# TrebleBoost.net
KiCad netlist of a schematic drawn in Altium Designer
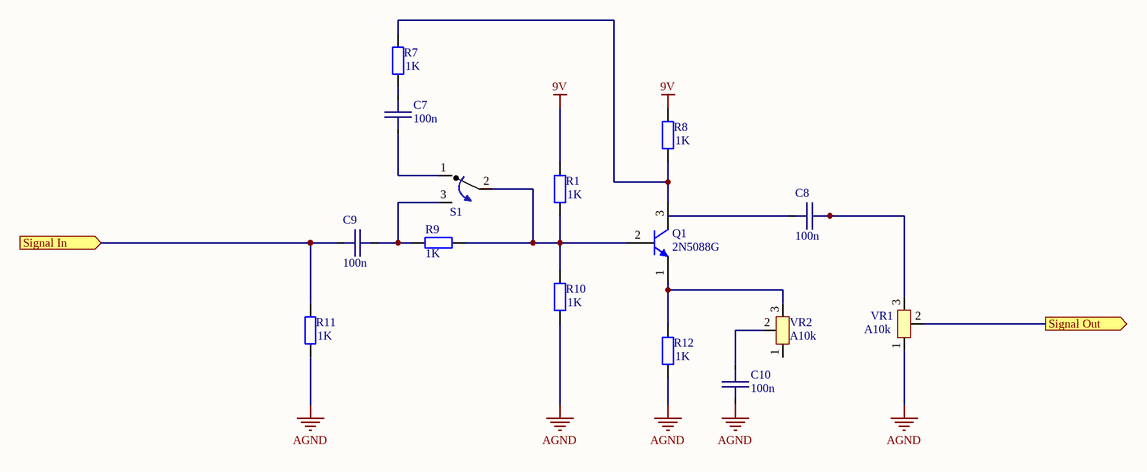
[diagram p0: TrebleBoost.SchDoc]

(export (version "E")
  (design (tool "Eeschema 10.0.6"))
  (components
    (comp (ref "C7")
      (value "100n")
      (footprint "Cap-0.2\"")
      (fields (field (name "Comment") "Wima Capacitor"))
      (libsource (lib "Parts") (part "Wima Capacitor"))
    )
    (comp (ref "C8")
      (value "100n")
      (footprint "Cap-0.2\"")
      (fields (field (name "Comment") "Wima Capacitor"))
      (libsource (lib "Parts") (part "Wima Capacitor"))
    )
    (comp (ref "C9")
      (value "100n")
      (footprint "Cap-0.2\"")
      (fields (field (name "Comment") "Wima Capacitor"))
      (libsource (lib "Parts") (part "Wima Capacitor"))
    )
    (comp (ref "C10")
      (value "100n")
      (footprint "Cap-0.2\"")
      (fields (field (name "Comment") "Wima Capacitor"))
      (libsource (lib "Parts") (part "Wima Capacitor"))
    )
    (comp (ref "Q1")
      (value "2N5088G")
      (footprint "ONSC-TO-92-3-29-11")
      (description "Amplifier Transistor, NPN Silicon, 3-Pin TO-92, Pb-Free, Bulk Box")
      (fields (field (name "MANUFACTURER") "On Semiconductor"))
      (libsource (lib "ON Semi General Purpose Transistors") (part "2N5088G"))
    )
    (comp (ref "R1")
      (value "1K")
      (footprint "AXIAL-0.4")
      (description "Resistor")
      (fields (field (name "Comment") "Res2") (field (name "PUBLISHER") "Altium Limited"))
      (libsource (lib "Miscellaneous Devices") (part "Res2"))
    )
    (comp (ref "R7")
      (value "1K")
      (footprint "AXIAL-0.4")
      (description "Resistor")
      (fields (field (name "Comment") "Res2") (field (name "PUBLISHER") "Altium Limited"))
      (libsource (lib "Miscellaneous Devices") (part "Res2"))
    )
    (comp (ref "R8")
      (value "1K")
      (footprint "AXIAL-0.4")
      (description "Resistor")
      (fields (field (name "Comment") "Res2") (field (name "PUBLISHER") "Altium Limited"))
      (libsource (lib "Miscellaneous Devices") (part "Res2"))
    )
    (comp (ref "R9")
      (value "1K")
      (footprint "AXIAL-0.4")
      (description "Resistor")
      (fields (field (name "Comment") "Res2") (field (name "PUBLISHER") "Altium Limited"))
      (libsource (lib "") (part "Res2_1"))
    )
    (comp (ref "R10")
      (value "1K")
      (footprint "AXIAL-0.4")
      (description "Resistor")
      (fields (field (name "Comment") "Res2") (field (name "PUBLISHER") "Altium Limited"))
      (libsource (lib "Miscellaneous Devices") (part "Res2"))
    )
    (comp (ref "R11")
      (value "1K")
      (footprint "AXIAL-0.4")
      (description "Resistor")
      (fields (field (name "Comment") "Res2") (field (name "PUBLISHER") "Altium Limited"))
      (libsource (lib "Miscellaneous Devices") (part "Res2"))
    )
    (comp (ref "R12")
      (value "1K")
      (footprint "AXIAL-0.4")
      (description "Resistor")
      (fields (field (name "Comment") "Res2") (field (name "PUBLISHER") "Altium Limited"))
      (libsource (lib "Miscellaneous Devices") (part "Res2"))
    )
    (comp (ref "S1")
      (value "SPDT Toggle")
      (footprint "SPDT Toggle")
      (libsource (lib "Parts") (part "SPDT Toggle"))
    )
    (comp (ref "VR1")
      (value "A10k")
      (footprint "Pot-16mm")
      (fields (field (name "Comment") "Pot-16mm"))
      (libsource (lib "") (part "Pot-16mm_1"))
    )
    (comp (ref "VR2")
      (value "A10k")
      (footprint "Pot-16mm")
      (fields (field (name "Comment") "Pot-16mm"))
      (libsource (lib "Parts") (part "Pot-16mm"))
    )
  )
  (nets
    (net (code "1") (name "/Signal In") (class "Default")
      (node (ref "C9") (pin "2") (pinfunction "2_2") (pintype "passive"))
      (node (ref "R11") (pin "2") (pinfunction "2_2") (pintype "passive"))
    )
    (net (code "2") (name "/Signal Out") (class "Default")
      (node (ref "VR1") (pin "2") (pinfunction "2_2") (pintype "passive"))
    )
    (net (code "3") (name "9V") (class "Default")
      (node (ref "R1") (pin "2") (pinfunction "2_2") (pintype "passive"))
      (node (ref "R8") (pin "2") (pinfunction "2_2") (pintype "passive"))
    )
    (net (code "4") (name "AGND") (class "Default")
      (node (ref "C10") (pin "1") (pinfunction "1_1") (pintype "passive"))
      (node (ref "R10") (pin "1") (pinfunction "1_1") (pintype "passive"))
      (node (ref "R11") (pin "1") (pinfunction "1_1") (pintype "passive"))
      (node (ref "R12") (pin "1") (pinfunction "1_1") (pintype "passive"))
      (node (ref "VR1") (pin "1") (pinfunction "1_1") (pintype "passive"))
    )
    (net (code "5") (name "Net-(C7-Pad1)") (class "Default")
      (node (ref "C7") (pin "1") (pinfunction "1_1") (pintype "passive"))
      (node (ref "R7") (pin "1") (pinfunction "1_1") (pintype "passive"))
    )
    (net (code "6") (name "Net-(C7-Pad2)") (class "Default")
      (node (ref "C7") (pin "2") (pinfunction "2_2") (pintype "passive"))
      (node (ref "S1") (pin "1") (pinfunction "1_1") (pintype "passive"))
    )
    (net (code "7") (name "Net-(C8-Pad1)") (class "Default")
      (node (ref "C8") (pin "1") (pinfunction "1_1") (pintype "passive"))
      (node (ref "VR1") (pin "3") (pinfunction "3_3") (pintype "passive"))
    )
    (net (code "8") (name "Net-(C9-Pad1)") (class "Default")
      (node (ref "C9") (pin "1") (pinfunction "1_1") (pintype "passive"))
      (node (ref "R9") (pin "2") (pinfunction "2_2") (pintype "passive"))
      (node (ref "S1") (pin "3") (pinfunction "3_3") (pintype "passive"))
    )
    (net (code "9") (name "Net-(C10-Pad2)") (class "Default")
      (node (ref "C10") (pin "2") (pinfunction "2_2") (pintype "passive"))
      (node (ref "VR2") (pin "2") (pinfunction "2_2") (pintype "passive"))
    )
    (net (code "10") (name "Net-(Q1-B)") (class "Default")
      (node (ref "Q1") (pin "2") (pinfunction "B_2") (pintype "passive"))
      (node (ref "R1") (pin "1") (pinfunction "1_1") (pintype "passive"))
      (node (ref "R10") (pin "2") (pinfunction "2_2") (pintype "passive"))
      (node (ref "R9") (pin "1") (pinfunction "1_1") (pintype "passive"))
      (node (ref "S1") (pin "2") (pinfunction "2_2") (pintype "passive"))
    )
    (net (code "11") (name "Net-(Q1-C)") (class "Default")
      (node (ref "Q1") (pin "3") (pinfunction "C_3") (pintype "passive"))
      (node (ref "R7") (pin "2") (pinfunction "2_2") (pintype "passive"))
      (node (ref "R8") (pin "1") (pinfunction "1_1") (pintype "passive"))
    )
    (net (code "12") (name "Net-(Q1-E)") (class "Default")
      (node (ref "Q1") (pin "1") (pinfunction "E_1") (pintype "passive"))
      (node (ref "R12") (pin "2") (pinfunction "2_2") (pintype "passive"))
      (node (ref "VR2") (pin "3") (pinfunction "3_3") (pintype "passive"))
    )
    (net (code "13") (name "unconnected-(C8-Pad2)") (class "Default")
      (node (ref "C8") (pin "2") (pinfunction "2_2") (pintype "passive"))
    )
    (net (code "14") (name "unconnected-(VR2-Pad1)") (class "Default")
      (node (ref "VR2") (pin "1") (pinfunction "1_1") (pintype "passive"))
    )
  )
)
